# controller.net
KiCad netlist of a schematic drawn in EAGLE
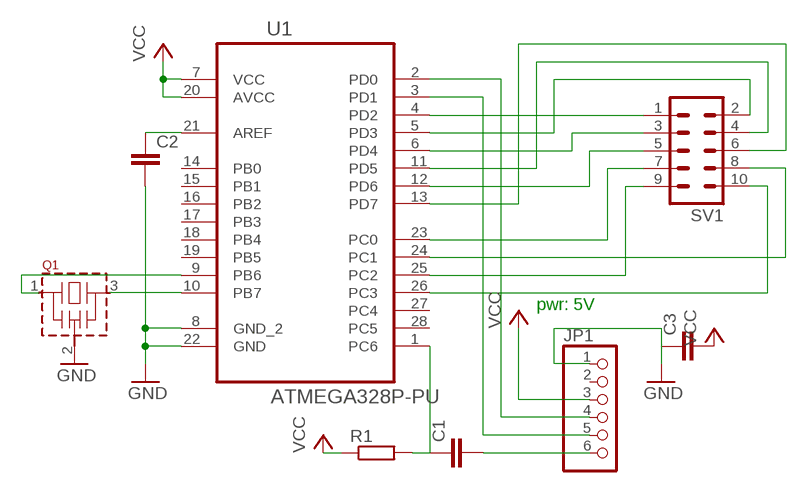
[diagram p0: schematic, sheet 1]

(export (version "E")
  (design (tool "Eeschema 10.0.6"))
  (components
    (comp (ref "C1")
      (value "C5/3.5")
      (footprint "eagle-import:C5B3.5")
      (libsource (lib "eagle-import") (part "C5/3.5"))
    )
    (comp (ref "C2")
      (value "C5/3.5")
      (footprint "eagle-import:C5B3.5")
      (libsource (lib "eagle-import") (part "C5/3.5"))
    )
    (comp (ref "C3")
      (value "C5/3.5")
      (footprint "eagle-import:C5B3.5")
      (libsource (lib "eagle-import") (part "C5/3.5"))
    )
    (comp (ref "JP1")
      (value "PINHD-1X6/90")
      (footprint "eagle-import:1X06_90")
      (libsource (lib "eagle-import") (part "PINHD-1X6/90"))
    )
    (comp (ref "Q1")
      (value "CSTLA_X")
      (footprint "eagle-import:CSTLA_T")
      (libsource (lib "eagle-import") (part "CSTLA_X"))
    )
    (comp (ref "R1")
      (value "R-EU_R0805")
      (footprint "eagle-import:R0805")
      (libsource (lib "eagle-import") (part "R-EU_R0805"))
    )
    (comp (ref "SV1")
      (value "MA05-2")
      (footprint "eagle-import:MA05-2")
      (libsource (lib "eagle-import") (part "MA05-2"))
    )
    (comp (ref "U1")
      (value "ATMEGA328P-PU")
      (footprint "eagle-import:DIP254P762X457-28")
      (libsource (lib "eagle-import") (part "ATMEGA328P-PU"))
    )
  )
  (nets
    (net (code "1") (name "GND") (class "Default")
      (node (ref "C2") (pin "2") (pinfunction "2_2") (pintype "passive"))
      (node (ref "C3") (pin "1") (pinfunction "1_1") (pintype "passive"))
      (node (ref "JP1") (pin "1") (pinfunction "1_1") (pintype "passive"))
      (node (ref "Q1") (pin "2") (pinfunction "VSS_2") (pintype "power_in"))
      (node (ref "U1") (pin "22") (pinfunction "GND_22") (pintype "passive"))
      (node (ref "U1") (pin "8") (pinfunction "GND_2_8") (pintype "passive"))
    )
    (net (code "2") (name "Net-(C1-Pad2)") (class "Default")
      (node (ref "C1") (pin "2") (pinfunction "2_2") (pintype "passive"))
      (node (ref "JP1") (pin "6") (pinfunction "6_6") (pintype "passive"))
    )
    (net (code "3") (name "Net-(U1-AREF)") (class "Default")
      (node (ref "C2") (pin "1") (pinfunction "1_1") (pintype "passive"))
      (node (ref "U1") (pin "21") (pinfunction "AREF_21") (pintype "input"))
    )
    (net (code "4") (name "Net-(U1-PB6)") (class "Default")
      (node (ref "Q1") (pin "1") (pinfunction "1_1") (pintype "output"))
      (node (ref "U1") (pin "9") (pinfunction "PB6_9") (pintype "bidirectional"))
    )
    (net (code "5") (name "Net-(U1-PB7)") (class "Default")
      (node (ref "Q1") (pin "3") (pinfunction "3_3") (pintype "input"))
      (node (ref "U1") (pin "10") (pinfunction "PB7_10") (pintype "bidirectional"))
    )
    (net (code "6") (name "Net-(U1-PC0)") (class "Default")
      (node (ref "SV1") (pin "7") (pinfunction "7_7") (pintype "passive"))
      (node (ref "U1") (pin "23") (pinfunction "PC0_23") (pintype "bidirectional"))
    )
    (net (code "7") (name "Net-(U1-PC1)") (class "Default")
      (node (ref "SV1") (pin "8") (pinfunction "8_8") (pintype "passive"))
      (node (ref "U1") (pin "24") (pinfunction "PC1_24") (pintype "bidirectional"))
    )
    (net (code "8") (name "Net-(U1-PC2)") (class "Default")
      (node (ref "SV1") (pin "9") (pinfunction "9_9") (pintype "passive"))
      (node (ref "U1") (pin "25") (pinfunction "PC2_25") (pintype "bidirectional"))
    )
    (net (code "9") (name "Net-(U1-PC3)") (class "Default")
      (node (ref "SV1") (pin "10") (pinfunction "10_10") (pintype "passive"))
      (node (ref "U1") (pin "26") (pinfunction "PC3_26") (pintype "bidirectional"))
    )
    (net (code "10") (name "Net-(U1-PC6)") (class "Default")
      (node (ref "C1") (pin "1") (pinfunction "1_1") (pintype "passive"))
      (node (ref "R1") (pin "2") (pinfunction "2_2") (pintype "passive"))
      (node (ref "U1") (pin "1") (pinfunction "PC6_1") (pintype "bidirectional"))
    )
    (net (code "11") (name "Net-(U1-PD0)") (class "Default")
      (node (ref "JP1") (pin "4") (pinfunction "4_4") (pintype "passive"))
      (node (ref "U1") (pin "2") (pinfunction "PD0_2") (pintype "bidirectional"))
    )
    (net (code "12") (name "Net-(U1-PD1)") (class "Default")
      (node (ref "JP1") (pin "5") (pinfunction "5_5") (pintype "passive"))
      (node (ref "U1") (pin "3") (pinfunction "PD1_3") (pintype "bidirectional"))
    )
    (net (code "13") (name "Net-(U1-PD2)") (class "Default")
      (node (ref "SV1") (pin "1") (pinfunction "1_1") (pintype "passive"))
      (node (ref "U1") (pin "4") (pinfunction "PD2_4") (pintype "bidirectional"))
    )
    (net (code "14") (name "Net-(U1-PD3)") (class "Default")
      (node (ref "SV1") (pin "2") (pinfunction "2_2") (pintype "passive"))
      (node (ref "U1") (pin "5") (pinfunction "PD3_5") (pintype "bidirectional"))
    )
    (net (code "15") (name "Net-(U1-PD4)") (class "Default")
      (node (ref "SV1") (pin "3") (pinfunction "3_3") (pintype "passive"))
      (node (ref "U1") (pin "6") (pinfunction "PD4_6") (pintype "bidirectional"))
    )
    (net (code "16") (name "Net-(U1-PD5)") (class "Default")
      (node (ref "SV1") (pin "4") (pinfunction "4_4") (pintype "passive"))
      (node (ref "U1") (pin "11") (pinfunction "PD5_11") (pintype "bidirectional"))
    )
    (net (code "17") (name "Net-(U1-PD6)") (class "Default")
      (node (ref "SV1") (pin "5") (pinfunction "5_5") (pintype "passive"))
      (node (ref "U1") (pin "12") (pinfunction "PD6_12") (pintype "bidirectional"))
    )
    (net (code "18") (name "Net-(U1-PD7)") (class "Default")
      (node (ref "SV1") (pin "6") (pinfunction "6_6") (pintype "passive"))
      (node (ref "U1") (pin "13") (pinfunction "PD7_13") (pintype "bidirectional"))
    )
    (net (code "19") (name "VCC") (class "Default")
      (node (ref "C3") (pin "2") (pinfunction "2_2") (pintype "passive"))
      (node (ref "JP1") (pin "3") (pinfunction "3_3") (pintype "passive"))
      (node (ref "R1") (pin "1") (pinfunction "1_1") (pintype "passive"))
      (node (ref "U1") (pin "20") (pinfunction "AVCC_20") (pintype "power_in"))
      (node (ref "U1") (pin "7") (pinfunction "VCC_7") (pintype "power_in"))
    )
    (net (code "20") (name "unconnected-(JP1-Pad2)") (class "Default")
      (node (ref "JP1") (pin "2") (pinfunction "2_2") (pintype "passive"))
    )
    (net (code "21") (name "unconnected-(U1-PB0-Pad14)") (class "Default")
      (node (ref "U1") (pin "14") (pinfunction "PB0_14") (pintype "bidirectional"))
    )
    (net (code "22") (name "unconnected-(U1-PB1-Pad15)") (class "Default")
      (node (ref "U1") (pin "15") (pinfunction "PB1_15") (pintype "bidirectional"))
    )
    (net (code "23") (name "unconnected-(U1-PB2-Pad16)") (class "Default")
      (node (ref "U1") (pin "16") (pinfunction "PB2_16") (pintype "bidirectional"))
    )
    (net (code "24") (name "unconnected-(U1-PB3-Pad17)") (class "Default")
      (node (ref "U1") (pin "17") (pinfunction "PB3_17") (pintype "bidirectional"))
    )
    (net (code "25") (name "unconnected-(U1-PB4-Pad18)") (class "Default")
      (node (ref "U1") (pin "18") (pinfunction "PB4_18") (pintype "bidirectional"))
    )
    (net (code "26") (name "unconnected-(U1-PB5-Pad19)") (class "Default")
      (node (ref "U1") (pin "19") (pinfunction "PB5_19") (pintype "bidirectional"))
    )
    (net (code "27") (name "unconnected-(U1-PC4-Pad27)") (class "Default")
      (node (ref "U1") (pin "27") (pinfunction "PC4_27") (pintype "bidirectional"))
    )
    (net (code "28") (name "unconnected-(U1-PC5-Pad28)") (class "Default")
      (node (ref "U1") (pin "28") (pinfunction "PC5_28") (pintype "bidirectional"))
    )
  )
)
